# H3_MIDIController_Rev_3_MainBoard.net
KiCad netlist of a schematic drawn in EAGLE
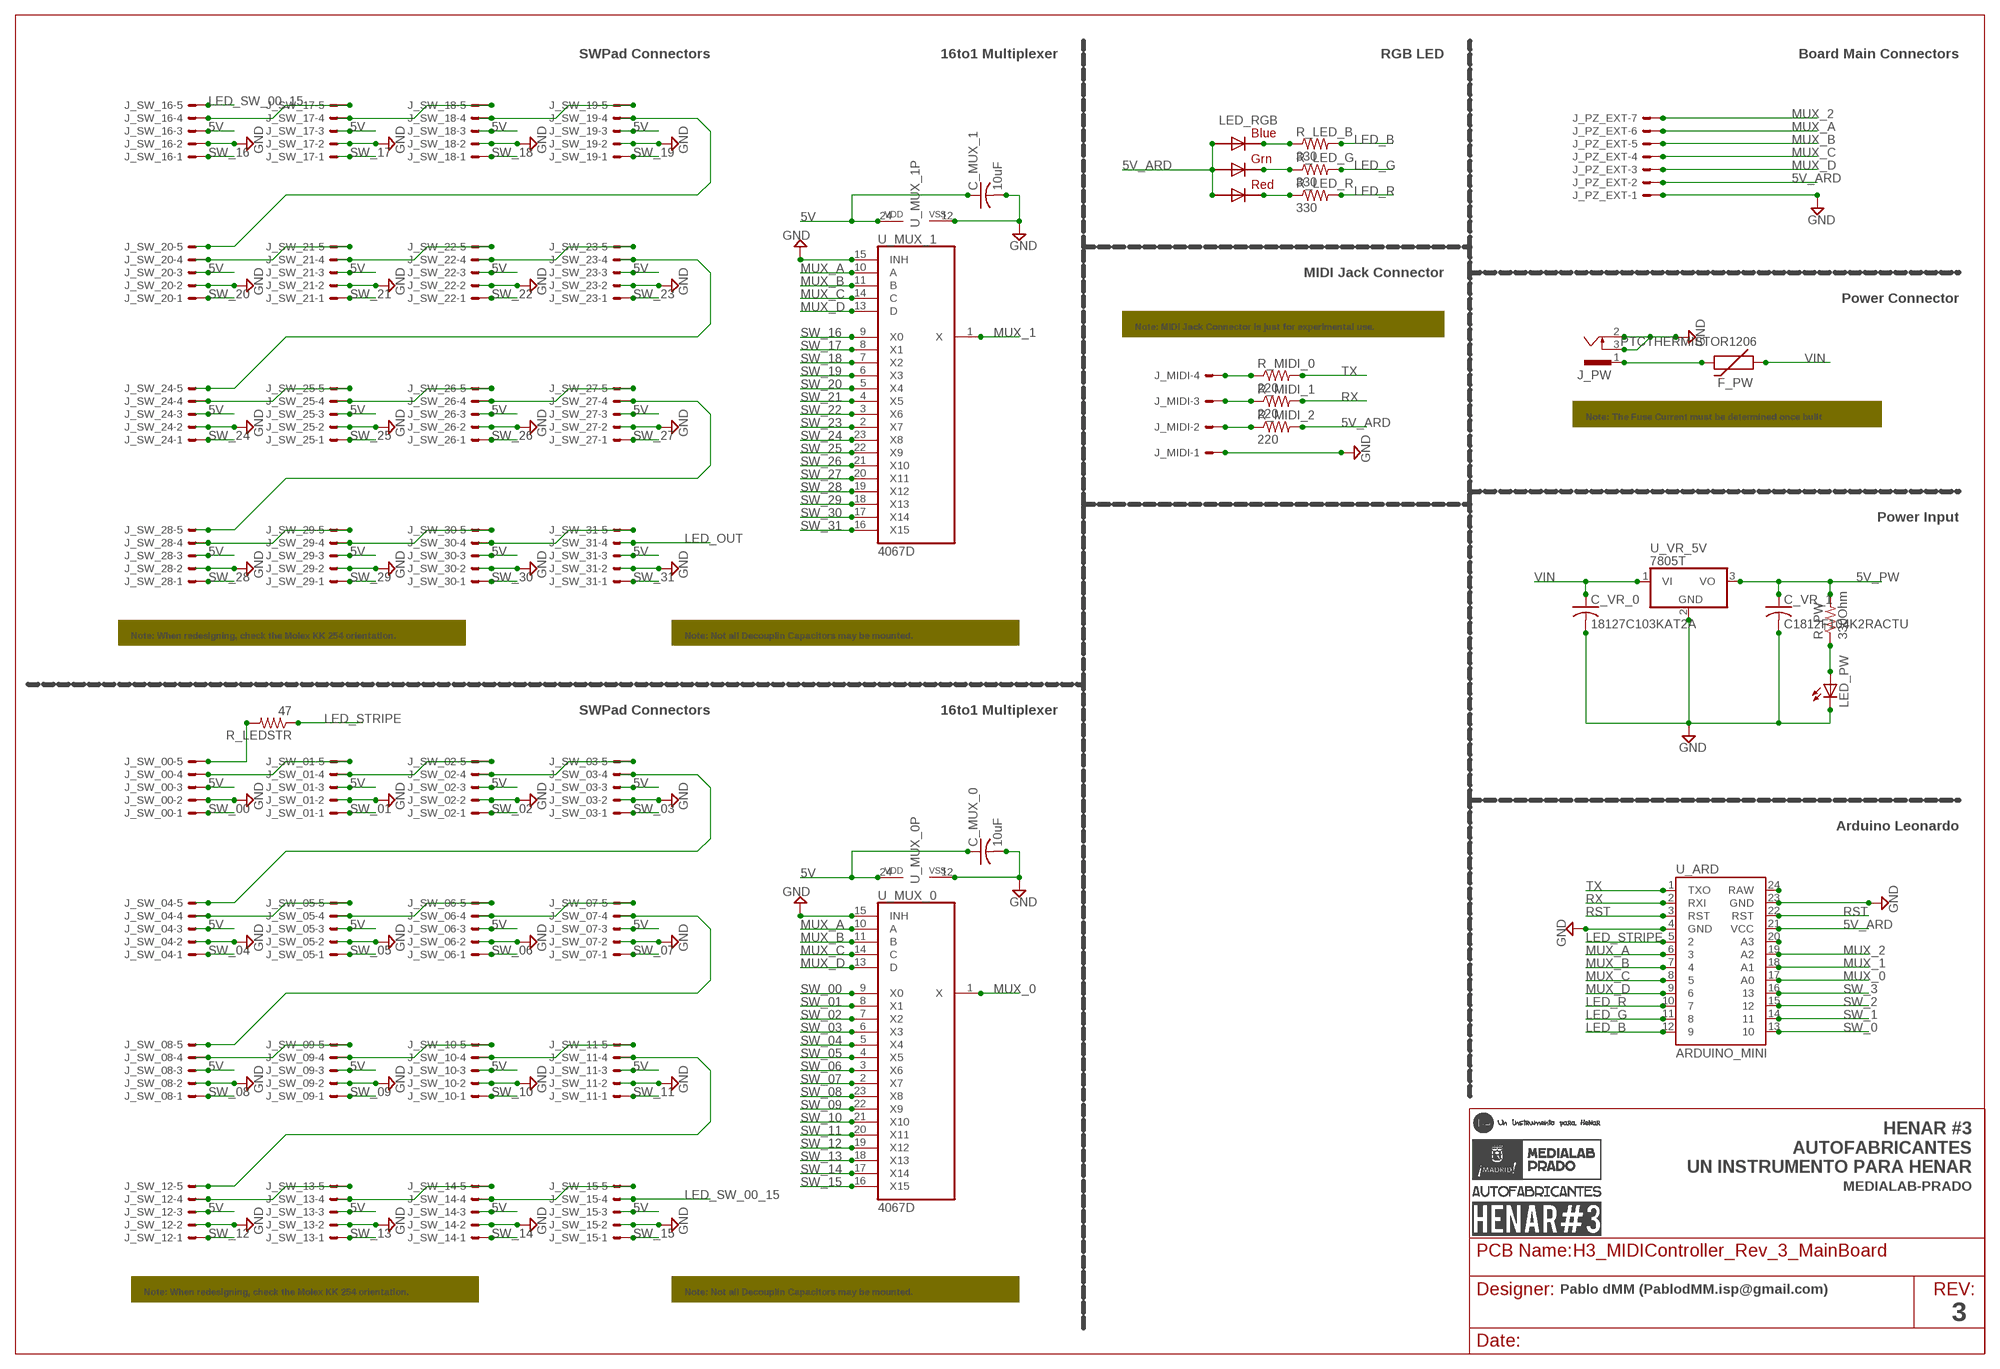
[diagram p0: schematic, sheet 1]

(export (version "E")
  (design (tool "Eeschema 10.0.6"))
  (components
    (comp (ref "C_MUX_0")
      (value "10uF")
      (footprint "eagle-import:C1206K")
      (libsource (lib "eagle-import") (part "C-USC1206K"))
    )
    (comp (ref "C_MUX_1")
      (value "10uF")
      (footprint "eagle-import:C1206K")
      (libsource (lib "eagle-import") (part "C-USC1206K"))
    )
    (comp (ref "C_VR_0")
      (value "18127C103KAT2A")
      (footprint "eagle-import:C1812K")
      (libsource (lib "eagle-import") (part "C-USC1812K"))
    )
    (comp (ref "C_VR_1")
      (value "C1812F104K2RACTU")
      (footprint "eagle-import:C1812K")
      (libsource (lib "eagle-import") (part "C-USC1812K"))
    )
    (comp (ref "F_PW")
      (value "PTCTHERMISTOR1206")
      (footprint "eagle-import:PTC-1206")
      (libsource (lib "eagle-import") (part "PTCTHERMISTOR1206"))
    )
    (comp (ref "J_MIDI")
      (value "22-05-7048-04")
      (footprint "eagle-import:7395-04")
      (libsource (lib "eagle-import") (part "22-?-0405-7048"))
    )
    (comp (ref "J_PW")
      (value "SCD-014A")
      (footprint "eagle-import:SCD-014-A")
      (libsource (lib "eagle-import") (part "SCD-014A"))
    )
    (comp (ref "J_PZ_EXT")
      (value "22-05-7078-07")
      (footprint "eagle-import:7395-07")
      (libsource (lib "eagle-import") (part "22-?-0705-7078"))
    )
    (comp (ref "J_SW_00")
      (value "22-05-7058-05")
      (footprint "eagle-import:7395-05")
      (libsource (lib "eagle-import") (part "22-?-0505-7058"))
    )
    (comp (ref "J_SW_01")
      (value "22-05-7058-05")
      (footprint "eagle-import:7395-05")
      (libsource (lib "eagle-import") (part "22-?-0505-7058"))
    )
    (comp (ref "J_SW_02")
      (value "22-05-7058-05")
      (footprint "eagle-import:7395-05")
      (libsource (lib "eagle-import") (part "22-?-0505-7058"))
    )
    (comp (ref "J_SW_03")
      (value "22-05-7058-05")
      (footprint "eagle-import:7395-05")
      (libsource (lib "eagle-import") (part "22-?-0505-7058"))
    )
    (comp (ref "J_SW_04")
      (value "22-05-7058-05")
      (footprint "eagle-import:7395-05")
      (libsource (lib "eagle-import") (part "22-?-0505-7058"))
    )
    (comp (ref "J_SW_05")
      (value "22-05-7058-05")
      (footprint "eagle-import:7395-05")
      (libsource (lib "eagle-import") (part "22-?-0505-7058"))
    )
    (comp (ref "J_SW_06")
      (value "22-05-7058-05")
      (footprint "eagle-import:7395-05")
      (libsource (lib "eagle-import") (part "22-?-0505-7058"))
    )
    (comp (ref "J_SW_07")
      (value "22-05-7058-05")
      (footprint "eagle-import:7395-05")
      (libsource (lib "eagle-import") (part "22-?-0505-7058"))
    )
    (comp (ref "J_SW_08")
      (value "22-05-7058-05")
      (footprint "eagle-import:7395-05")
      (libsource (lib "eagle-import") (part "22-?-0505-7058"))
    )
    (comp (ref "J_SW_09")
      (value "22-05-7058-05")
      (footprint "eagle-import:7395-05")
      (libsource (lib "eagle-import") (part "22-?-0505-7058"))
    )
    (comp (ref "J_SW_10")
      (value "22-05-7058-05")
      (footprint "eagle-import:7395-05")
      (libsource (lib "eagle-import") (part "22-?-0505-7058"))
    )
    (comp (ref "J_SW_11")
      (value "22-05-7058-05")
      (footprint "eagle-import:7395-05")
      (libsource (lib "eagle-import") (part "22-?-0505-7058"))
    )
    (comp (ref "J_SW_12")
      (value "22-05-7058-05")
      (footprint "eagle-import:7395-05")
      (libsource (lib "eagle-import") (part "22-?-0505-7058"))
    )
    (comp (ref "J_SW_13")
      (value "22-05-7058-05")
      (footprint "eagle-import:7395-05")
      (libsource (lib "eagle-import") (part "22-?-0505-7058"))
    )
    (comp (ref "J_SW_14")
      (value "22-05-7058-05")
      (footprint "eagle-import:7395-05")
      (libsource (lib "eagle-import") (part "22-?-0505-7058"))
    )
    (comp (ref "J_SW_15")
      (value "22-05-7058-05")
      (footprint "eagle-import:7395-05")
      (libsource (lib "eagle-import") (part "22-?-0505-7058"))
    )
    (comp (ref "J_SW_16")
      (value "22-05-7058-05")
      (footprint "eagle-import:7395-05")
      (libsource (lib "eagle-import") (part "22-?-0505-7058"))
    )
    (comp (ref "J_SW_17")
      (value "22-05-7058-05")
      (footprint "eagle-import:7395-05")
      (libsource (lib "eagle-import") (part "22-?-0505-7058"))
    )
    (comp (ref "J_SW_18")
      (value "22-05-7058-05")
      (footprint "eagle-import:7395-05")
      (libsource (lib "eagle-import") (part "22-?-0505-7058"))
    )
    (comp (ref "J_SW_19")
      (value "22-05-7058-05")
      (footprint "eagle-import:7395-05")
      (libsource (lib "eagle-import") (part "22-?-0505-7058"))
    )
    (comp (ref "J_SW_20")
      (value "22-05-7058-05")
      (footprint "eagle-import:7395-05")
      (libsource (lib "eagle-import") (part "22-?-0505-7058"))
    )
    (comp (ref "J_SW_21")
      (value "22-05-7058-05")
      (footprint "eagle-import:7395-05")
      (libsource (lib "eagle-import") (part "22-?-0505-7058"))
    )
    (comp (ref "J_SW_22")
      (value "22-05-7058-05")
      (footprint "eagle-import:7395-05")
      (libsource (lib "eagle-import") (part "22-?-0505-7058"))
    )
    (comp (ref "J_SW_23")
      (value "22-05-7058-05")
      (footprint "eagle-import:7395-05")
      (libsource (lib "eagle-import") (part "22-?-0505-7058"))
    )
    (comp (ref "J_SW_24")
      (value "22-05-7058-05")
      (footprint "eagle-import:7395-05")
      (libsource (lib "eagle-import") (part "22-?-0505-7058"))
    )
    (comp (ref "J_SW_25")
      (value "22-05-7058-05")
      (footprint "eagle-import:7395-05")
      (libsource (lib "eagle-import") (part "22-?-0505-7058"))
    )
    (comp (ref "J_SW_26")
      (value "22-05-7058-05")
      (footprint "eagle-import:7395-05")
      (libsource (lib "eagle-import") (part "22-?-0505-7058"))
    )
    (comp (ref "J_SW_27")
      (value "22-05-7058-05")
      (footprint "eagle-import:7395-05")
      (libsource (lib "eagle-import") (part "22-?-0505-7058"))
    )
    (comp (ref "J_SW_28")
      (value "22-05-7058-05")
      (footprint "eagle-import:7395-05")
      (libsource (lib "eagle-import") (part "22-?-0505-7058"))
    )
    (comp (ref "J_SW_29")
      (value "22-05-7058-05")
      (footprint "eagle-import:7395-05")
      (libsource (lib "eagle-import") (part "22-?-0505-7058"))
    )
    (comp (ref "J_SW_30")
      (value "22-05-7058-05")
      (footprint "eagle-import:7395-05")
      (libsource (lib "eagle-import") (part "22-?-0505-7058"))
    )
    (comp (ref "J_SW_31")
      (value "22-05-7058-05")
      (footprint "eagle-import:7395-05")
      (libsource (lib "eagle-import") (part "22-?-0505-7058"))
    )
    (comp (ref "LED_PW")
      (value "LEDSMT1206")
      (footprint "eagle-import:1206")
      (libsource (lib "eagle-import") (part "LEDSMT1206"))
    )
    (comp (ref "LED_RGB")
      (value "RGBLED5050")
      (footprint "eagle-import:RGBLED5050")
      (libsource (lib "eagle-import") (part "RGBLED5050"))
    )
    (comp (ref "R_LEDSTR")
      (value "47")
      (footprint "eagle-import:M1206")
      (libsource (lib "eagle-import") (part "R-US_M1206"))
    )
    (comp (ref "R_LED_B")
      (value "330")
      (footprint "eagle-import:M1206")
      (libsource (lib "eagle-import") (part "R-US_M1206"))
    )
    (comp (ref "R_LED_G")
      (value "330")
      (footprint "eagle-import:M1206")
      (libsource (lib "eagle-import") (part "R-US_M1206"))
    )
    (comp (ref "R_LED_R")
      (value "330")
      (footprint "eagle-import:M1206")
      (libsource (lib "eagle-import") (part "R-US_M1206"))
    )
    (comp (ref "R_MIDI_0")
      (value "220")
      (footprint "eagle-import:M1206")
      (libsource (lib "eagle-import") (part "R-US_M1206"))
    )
    (comp (ref "R_MIDI_1")
      (value "220")
      (footprint "eagle-import:M1206")
      (libsource (lib "eagle-import") (part "R-US_M1206"))
    )
    (comp (ref "R_MIDI_2")
      (value "220")
      (footprint "eagle-import:M1206")
      (libsource (lib "eagle-import") (part "R-US_M1206"))
    )
    (comp (ref "R_PW")
      (value "330Ohm")
      (footprint "eagle-import:M1206")
      (libsource (lib "eagle-import") (part "R-US_M1206"))
    )
    (comp (ref "U_ARD")
      (value "ARDUINO_MINI")
      (footprint "eagle-import:ARDUINO_MINI")
      (libsource (lib "eagle-import") (part "ARDUINO_MINI"))
    )
    (comp (ref "U_MUX_0")
      (value "4067D")
      (footprint "eagle-import:SO24W")
      (libsource (lib "eagle-import") (part "4067D"))
    )
    (comp (ref "U_MUX_1")
      (value "4067D")
      (footprint "eagle-import:SO24W")
      (libsource (lib "eagle-import") (part "4067D"))
    )
    (comp (ref "U_VR_5V")
      (value "7805T")
      (footprint "eagle-import:TO220H")
      (libsource (lib "eagle-import") (part "78T05"))
    )
  )
  (nets
    (net (code "1") (name "/5V") (class "Default")
      (node (ref "C_MUX_0") (pin "1") (pinfunction "1_1") (pintype "passive"))
      (node (ref "C_MUX_1") (pin "1") (pinfunction "1_1") (pintype "passive"))
      (node (ref "J_SW_00") (pin "3") (pinfunction "S_3") (pintype "passive"))
      (node (ref "J_SW_01") (pin "3") (pinfunction "S_3") (pintype "passive"))
      (node (ref "J_SW_02") (pin "3") (pinfunction "S_3") (pintype "passive"))
      (node (ref "J_SW_03") (pin "3") (pinfunction "S_3") (pintype "passive"))
      (node (ref "J_SW_04") (pin "3") (pinfunction "S_3") (pintype "passive"))
      (node (ref "J_SW_05") (pin "3") (pinfunction "S_3") (pintype "passive"))
      (node (ref "J_SW_06") (pin "3") (pinfunction "S_3") (pintype "passive"))
      (node (ref "J_SW_07") (pin "3") (pinfunction "S_3") (pintype "passive"))
      (node (ref "J_SW_08") (pin "3") (pinfunction "S_3") (pintype "passive"))
      (node (ref "J_SW_09") (pin "3") (pinfunction "S_3") (pintype "passive"))
      (node (ref "J_SW_10") (pin "3") (pinfunction "S_3") (pintype "passive"))
      (node (ref "J_SW_11") (pin "3") (pinfunction "S_3") (pintype "passive"))
      (node (ref "J_SW_12") (pin "3") (pinfunction "S_3") (pintype "passive"))
      (node (ref "J_SW_13") (pin "3") (pinfunction "S_3") (pintype "passive"))
      (node (ref "J_SW_14") (pin "3") (pinfunction "S_3") (pintype "passive"))
      (node (ref "J_SW_15") (pin "3") (pinfunction "S_3") (pintype "passive"))
      (node (ref "J_SW_16") (pin "3") (pinfunction "S_3") (pintype "passive"))
      (node (ref "J_SW_17") (pin "3") (pinfunction "S_3") (pintype "passive"))
      (node (ref "J_SW_18") (pin "3") (pinfunction "S_3") (pintype "passive"))
      (node (ref "J_SW_19") (pin "3") (pinfunction "S_3") (pintype "passive"))
      (node (ref "J_SW_20") (pin "3") (pinfunction "S_3") (pintype "passive"))
      (node (ref "J_SW_21") (pin "3") (pinfunction "S_3") (pintype "passive"))
      (node (ref "J_SW_22") (pin "3") (pinfunction "S_3") (pintype "passive"))
      (node (ref "J_SW_23") (pin "3") (pinfunction "S_3") (pintype "passive"))
      (node (ref "J_SW_24") (pin "3") (pinfunction "S_3") (pintype "passive"))
      (node (ref "J_SW_25") (pin "3") (pinfunction "S_3") (pintype "passive"))
      (node (ref "J_SW_26") (pin "3") (pinfunction "S_3") (pintype "passive"))
      (node (ref "J_SW_27") (pin "3") (pinfunction "S_3") (pintype "passive"))
      (node (ref "J_SW_28") (pin "3") (pinfunction "S_3") (pintype "passive"))
      (node (ref "J_SW_29") (pin "3") (pinfunction "S_3") (pintype "passive"))
      (node (ref "J_SW_30") (pin "3") (pinfunction "S_3") (pintype "passive"))
      (node (ref "J_SW_31") (pin "3") (pinfunction "S_3") (pintype "passive"))
      (node (ref "U_MUX_0") (pin "24") (pinfunction "VDD_24") (pintype "power_in"))
      (node (ref "U_MUX_1") (pin "24") (pinfunction "VDD_24") (pintype "power_in"))
    )
    (net (code "2") (name "/5V_ARD") (class "Default")
      (node (ref "J_PZ_EXT") (pin "2") (pinfunction "S_2") (pintype "passive"))
      (node (ref "LED_RGB") (pin "1") (pinfunction "GREEN_A_1") (pintype "bidirectional"))
      (node (ref "LED_RGB") (pin "2") (pinfunction "RED_A_2") (pintype "bidirectional"))
      (node (ref "LED_RGB") (pin "3") (pinfunction "BLUE_A_3") (pintype "bidirectional"))
      (node (ref "R_MIDI_2") (pin "2") (pinfunction "2_2") (pintype "passive"))
      (node (ref "U_ARD") (pin "21") (pinfunction "VCC_21") (pintype "bidirectional"))
    )
    (net (code "3") (name "/5V_PW") (class "Default")
      (node (ref "C_VR_1") (pin "1") (pinfunction "1_1") (pintype "passive"))
      (node (ref "R_PW") (pin "2") (pinfunction "2_2") (pintype "passive"))
      (node (ref "U_VR_5V") (pin "3") (pinfunction "VO_3") (pintype "passive"))
    )
    (net (code "4") (name "/LED_B") (class "Default")
      (node (ref "R_LED_B") (pin "2") (pinfunction "2_2") (pintype "passive"))
      (node (ref "U_ARD") (pin "12") (pinfunction "9_12") (pintype "bidirectional"))
    )
    (net (code "5") (name "/LED_G") (class "Default")
      (node (ref "R_LED_G") (pin "2") (pinfunction "2_2") (pintype "passive"))
      (node (ref "U_ARD") (pin "11") (pinfunction "8_11") (pintype "bidirectional"))
    )
    (net (code "6") (name "/LED_OUT") (class "Default")
      (node (ref "J_SW_31") (pin "4") (pinfunction "S_4") (pintype "passive"))
    )
    (net (code "7") (name "/LED_R") (class "Default")
      (node (ref "R_LED_R") (pin "2") (pinfunction "2_2") (pintype "passive"))
      (node (ref "U_ARD") (pin "10") (pinfunction "7_10") (pintype "bidirectional"))
    )
    (net (code "8") (name "/LED_STRIPE") (class "Default")
      (node (ref "R_LEDSTR") (pin "1") (pinfunction "1_1") (pintype "passive"))
      (node (ref "U_ARD") (pin "5") (pinfunction "2_5") (pintype "bidirectional"))
    )
    (net (code "9") (name "/LED_SW_00_15") (class "Default")
      (node (ref "J_SW_15") (pin "4") (pinfunction "S_4") (pintype "passive"))
      (node (ref "J_SW_16") (pin "5") (pinfunction "S_5") (pintype "passive"))
    )
    (net (code "10") (name "/MUX_0") (class "Default")
      (node (ref "U_ARD") (pin "17") (pinfunction "A0_17") (pintype "bidirectional"))
      (node (ref "U_MUX_0") (pin "1") (pinfunction "X_1") (pintype "output"))
    )
    (net (code "11") (name "/MUX_1") (class "Default")
      (node (ref "U_ARD") (pin "18") (pinfunction "A1_18") (pintype "bidirectional"))
      (node (ref "U_MUX_1") (pin "1") (pinfunction "X_1") (pintype "output"))
    )
    (net (code "12") (name "/MUX_2") (class "Default")
      (node (ref "J_PZ_EXT") (pin "7") (pinfunction "S_7") (pintype "passive"))
      (node (ref "U_ARD") (pin "19") (pinfunction "A2_19") (pintype "bidirectional"))
    )
    (net (code "13") (name "/MUX_A") (class "Default")
      (node (ref "J_PZ_EXT") (pin "6") (pinfunction "S_6") (pintype "passive"))
      (node (ref "U_ARD") (pin "6") (pinfunction "3_6") (pintype "bidirectional"))
      (node (ref "U_MUX_0") (pin "10") (pinfunction "A_10") (pintype "input"))
      (node (ref "U_MUX_1") (pin "10") (pinfunction "A_10") (pintype "input"))
    )
    (net (code "14") (name "/MUX_B") (class "Default")
      (node (ref "J_PZ_EXT") (pin "5") (pinfunction "S_5") (pintype "passive"))
      (node (ref "U_ARD") (pin "7") (pinfunction "4_7") (pintype "bidirectional"))
      (node (ref "U_MUX_0") (pin "11") (pinfunction "B_11") (pintype "input"))
      (node (ref "U_MUX_1") (pin "11") (pinfunction "B_11") (pintype "input"))
    )
    (net (code "15") (name "/MUX_C") (class "Default")
      (node (ref "J_PZ_EXT") (pin "4") (pinfunction "S_4") (pintype "passive"))
      (node (ref "U_ARD") (pin "8") (pinfunction "5_8") (pintype "bidirectional"))
      (node (ref "U_MUX_0") (pin "14") (pinfunction "C_14") (pintype "input"))
      (node (ref "U_MUX_1") (pin "14") (pinfunction "C_14") (pintype "input"))
    )
    (net (code "16") (name "/MUX_D") (class "Default")
      (node (ref "J_PZ_EXT") (pin "3") (pinfunction "S_3") (pintype "passive"))
      (node (ref "U_ARD") (pin "9") (pinfunction "6_9") (pintype "bidirectional"))
      (node (ref "U_MUX_0") (pin "13") (pinfunction "D_13") (pintype "input"))
      (node (ref "U_MUX_1") (pin "13") (pinfunction "D_13") (pintype "input"))
    )
    (net (code "17") (name "/RST") (class "Default")
      (node (ref "U_ARD") (pin "22") (pinfunction "RST_22") (pintype "bidirectional"))
      (node (ref "U_ARD") (pin "3") (pinfunction "RST_3") (pintype "bidirectional"))
    )
    (net (code "18") (name "/RX") (class "Default")
      (node (ref "R_MIDI_1") (pin "2") (pinfunction "2_2") (pintype "passive"))
      (node (ref "U_ARD") (pin "2") (pinfunction "RXI_2") (pintype "bidirectional"))
    )
    (net (code "19") (name "/SW_00") (class "Default")
      (node (ref "J_SW_00") (pin "1") (pinfunction "S_1") (pintype "passive"))
      (node (ref "U_MUX_0") (pin "9") (pinfunction "X0_9") (pintype "input"))
    )
    (net (code "20") (name "/SW_0") (class "Default")
      (node (ref "U_ARD") (pin "13") (pinfunction "10_13") (pintype "bidirectional"))
    )
    (net (code "21") (name "/SW_1") (class "Default")
      (node (ref "U_ARD") (pin "14") (pinfunction "11_14") (pintype "bidirectional"))
    )
    (net (code "22") (name "/SW_01") (class "Default")
      (node (ref "J_SW_01") (pin "1") (pinfunction "S_1") (pintype "passive"))
      (node (ref "U_MUX_0") (pin "8") (pinfunction "X1_8") (pintype "input"))
    )
    (net (code "23") (name "/SW_2") (class "Default")
      (node (ref "U_ARD") (pin "15") (pinfunction "12_15") (pintype "bidirectional"))
    )
    (net (code "24") (name "/SW_02") (class "Default")
      (node (ref "J_SW_02") (pin "1") (pinfunction "S_1") (pintype "passive"))
      (node (ref "U_MUX_0") (pin "7") (pinfunction "X2_7") (pintype "input"))
    )
    (net (code "25") (name "/SW_3") (class "Default")
      (node (ref "U_ARD") (pin "16") (pinfunction "13_16") (pintype "bidirectional"))
    )
    (net (code "26") (name "/SW_03") (class "Default")
      (node (ref "J_SW_03") (pin "1") (pinfunction "S_1") (pintype "passive"))
      (node (ref "U_MUX_0") (pin "6") (pinfunction "X3_6") (pintype "input"))
    )
    (net (code "27") (name "/SW_04") (class "Default")
      (node (ref "J_SW_04") (pin "1") (pinfunction "S_1") (pintype "passive"))
      (node (ref "U_MUX_0") (pin "5") (pinfunction "X4_5") (pintype "input"))
    )
    (net (code "28") (name "/SW_05") (class "Default")
      (node (ref "J_SW_05") (pin "1") (pinfunction "S_1") (pintype "passive"))
      (node (ref "U_MUX_0") (pin "4") (pinfunction "X5_4") (pintype "input"))
    )
    (net (code "29") (name "/SW_06") (class "Default")
      (node (ref "J_SW_06") (pin "1") (pinfunction "S_1") (pintype "passive"))
      (node (ref "U_MUX_0") (pin "3") (pinfunction "X6_3") (pintype "input"))
    )
    (net (code "30") (name "/SW_07") (class "Default")
      (node (ref "J_SW_07") (pin "1") (pinfunction "S_1") (pintype "passive"))
      (node (ref "U_MUX_0") (pin "2") (pinfunction "X7_2") (pintype "input"))
    )
    (net (code "31") (name "/SW_08") (class "Default")
      (node (ref "J_SW_08") (pin "1") (pinfunction "S_1") (pintype "passive"))
      (node (ref "U_MUX_0") (pin "23") (pinfunction "X8_23") (pintype "input"))
    )
    (net (code "32") (name "/SW_09") (class "Default")
      (node (ref "J_SW_09") (pin "1") (pinfunction "S_1") (pintype "passive"))
      (node (ref "U_MUX_0") (pin "22") (pinfunction "X9_22") (pintype "input"))
    )
    (net (code "33") (name "/SW_10") (class "Default")
      (node (ref "J_SW_10") (pin "1") (pinfunction "S_1") (pintype "passive"))
      (node (ref "U_MUX_0") (pin "21") (pinfunction "X10_21") (pintype "input"))
    )
    (net (code "34") (name "/SW_11") (class "Default")
      (node (ref "J_SW_11") (pin "1") (pinfunction "S_1") (pintype "passive"))
      (node (ref "U_MUX_0") (pin "20") (pinfunction "X11_20") (pintype "input"))
    )
    (net (code "35") (name "/SW_12") (class "Default")
      (node (ref "J_SW_12") (pin "1") (pinfunction "S_1") (pintype "passive"))
      (node (ref "U_MUX_0") (pin "19") (pinfunction "X12_19") (pintype "input"))
    )
    (net (code "36") (name "/SW_13") (class "Default")
      (node (ref "J_SW_13") (pin "1") (pinfunction "S_1") (pintype "passive"))
      (node (ref "U_MUX_0") (pin "18") (pinfunction "X13_18") (pintype "input"))
    )
    (net (code "37") (name "/SW_14") (class "Default")
      (node (ref "J_SW_14") (pin "1") (pinfunction "S_1") (pintype "passive"))
      (node (ref "U_MUX_0") (pin "17") (pinfunction "X14_17") (pintype "input"))
    )
    (net (code "38") (name "/SW_15") (class "Default")
      (node (ref "J_SW_15") (pin "1") (pinfunction "S_1") (pintype "passive"))
      (node (ref "U_MUX_0") (pin "16") (pinfunction "X15_16") (pintype "input"))
    )
    (net (code "39") (name "/SW_16") (class "Default")
      (node (ref "J_SW_16") (pin "1") (pinfunction "S_1") (pintype "passive"))
      (node (ref "U_MUX_1") (pin "9") (pinfunction "X0_9") (pintype "input"))
    )
    (net (code "40") (name "/SW_17") (class "Default")
      (node (ref "J_SW_17") (pin "1") (pinfunction "S_1") (pintype "passive"))
      (node (ref "U_MUX_1") (pin "8") (pinfunction "X1_8") (pintype "input"))
    )
    (net (code "41") (name "/SW_18") (class "Default")
      (node (ref "J_SW_18") (pin "1") (pinfunction "S_1") (pintype "passive"))
      (node (ref "U_MUX_1") (pin "7") (pinfunction "X2_7") (pintype "input"))
    )
    (net (code "42") (name "/SW_19") (class "Default")
      (node (ref "J_SW_19") (pin "1") (pinfunction "S_1") (pintype "passive"))
      (node (ref "U_MUX_1") (pin "6") (pinfunction "X3_6") (pintype "input"))
    )
    (net (code "43") (name "/SW_20") (class "Default")
      (node (ref "J_SW_20") (pin "1") (pinfunction "S_1") (pintype "passive"))
      (node (ref "U_MUX_1") (pin "5") (pinfunction "X4_5") (pintype "input"))
    )
    (net (code "44") (name "/SW_21") (class "Default")
      (node (ref "J_SW_21") (pin "1") (pinfunction "S_1") (pintype "passive"))
      (node (ref "U_MUX_1") (pin "4") (pinfunction "X5_4") (pintype "input"))
    )
    (net (code "45") (name "/SW_22") (class "Default")
      (node (ref "J_SW_22") (pin "1") (pinfunction "S_1") (pintype "passive"))
      (node (ref "U_MUX_1") (pin "3") (pinfunction "X6_3") (pintype "input"))
    )
    (net (code "46") (name "/SW_23") (class "Default")
      (node (ref "J_SW_23") (pin "1") (pinfunction "S_1") (pintype "passive"))
      (node (ref "U_MUX_1") (pin "2") (pinfunction "X7_2") (pintype "input"))
    )
    (net (code "47") (name "/SW_24") (class "Default")
      (node (ref "J_SW_24") (pin "1") (pinfunction "S_1") (pintype "passive"))
      (node (ref "U_MUX_1") (pin "23") (pinfunction "X8_23") (pintype "input"))
    )
    (net (code "48") (name "/SW_25") (class "Default")
      (node (ref "J_SW_25") (pin "1") (pinfunction "S_1") (pintype "passive"))
      (node (ref "U_MUX_1") (pin "22") (pinfunction "X9_22") (pintype "input"))
    )
    (net (code "49") (name "/SW_26") (class "Default")
      (node (ref "J_SW_26") (pin "1") (pinfunction "S_1") (pintype "passive"))
      (node (ref "U_MUX_1") (pin "21") (pinfunction "X10_21") (pintype "input"))
    )
    (net (code "50") (name "/SW_27") (class "Default")
      (node (ref "J_SW_27") (pin "1") (pinfunction "S_1") (pintype "passive"))
      (node (ref "U_MUX_1") (pin "20") (pinfunction "X11_20") (pintype "input"))
    )
    (net (code "51") (name "/SW_28") (class "Default")
      (node (ref "J_SW_28") (pin "1") (pinfunction "S_1") (pintype "passive"))
      (node (ref "U_MUX_1") (pin "19") (pinfunction "X12_19") (pintype "input"))
    )
    (net (code "52") (name "/SW_29") (class "Default")
      (node (ref "J_SW_29") (pin "1") (pinfunction "S_1") (pintype "passive"))
      (node (ref "U_MUX_1") (pin "18") (pinfunction "X13_18") (pintype "input"))
    )
    (net (code "53") (name "/SW_30") (class "Default")
      (node (ref "J_SW_30") (pin "1") (pinfunction "S_1") (pintype "passive"))
      (node (ref "U_MUX_1") (pin "17") (pinfunction "X14_17") (pintype "input"))
    )
    (net (code "54") (name "/SW_31") (class "Default")
      (node (ref "J_SW_31") (pin "1") (pinfunction "S_1") (pintype "passive"))
      (node (ref "U_MUX_1") (pin "16") (pinfunction "X15_16") (pintype "input"))
    )
    (net (code "55") (name "/TX") (class "Default")
      (node (ref "R_MIDI_0") (pin "2") (pinfunction "2_2") (pintype "passive"))
      (node (ref "U_ARD") (pin "1") (pinfunction "TXO_1") (pintype "bidirectional"))
    )
    (net (code "56") (name "/VIN") (class "Default")
      (node (ref "C_VR_0") (pin "1") (pinfunction "1_1") (pintype "passive"))
      (node (ref "F_PW") (pin "1") (pinfunction "1_1") (pintype "bidirectional"))
      (node (ref "U_VR_5V") (pin "1") (pinfunction "VI_1") (pintype "input"))
    )
    (net (code "57") (name "GND") (class "Default")
      (node (ref "C_MUX_0") (pin "2") (pinfunction "2_2") (pintype "passive"))
      (node (ref "C_MUX_1") (pin "2") (pinfunction "2_2") (pintype "passive"))
      (node (ref "C_VR_0") (pin "2") (pinfunction "2_2") (pintype "passive"))
      (node (ref "C_VR_1") (pin "2") (pinfunction "2_2") (pintype "passive"))
      (node (ref "J_MIDI") (pin "1") (pinfunction "S_1") (pintype "passive"))
      (node (ref "J_PW") (pin "2") (pinfunction "2_2") (pintype "passive"))
      (node (ref "J_PW") (pin "3") (pinfunction "3_3") (pintype "passive"))
      (node (ref "J_PZ_EXT") (pin "1") (pinfunction "S_1") (pintype "passive"))
      (node (ref "J_SW_00") (pin "2") (pinfunction "S_2") (pintype "passive"))
      (node (ref "J_SW_01") (pin "2") (pinfunction "S_2") (pintype "passive"))
      (node (ref "J_SW_02") (pin "2") (pinfunction "S_2") (pintype "passive"))
      (node (ref "J_SW_03") (pin "2") (pinfunction "S_2") (pintype "passive"))
      (node (ref "J_SW_04") (pin "2") (pinfunction "S_2") (pintype "passive"))
      (node (ref "J_SW_05") (pin "2") (pinfunction "S_2") (pintype "passive"))
      (node (ref "J_SW_06") (pin "2") (pinfunction "S_2") (pintype "passive"))
      (node (ref "J_SW_07") (pin "2") (pinfunction "S_2") (pintype "passive"))
      (node (ref "J_SW_08") (pin "2") (pinfunction "S_2") (pintype "passive"))
      (node (ref "J_SW_09") (pin "2") (pinfunction "S_2") (pintype "passive"))
      (node (ref "J_SW_10") (pin "2") (pinfunction "S_2") (pintype "passive"))
      (node (ref "J_SW_11") (pin "2") (pinfunction "S_2") (pintype "passive"))
      (node (ref "J_SW_12") (pin "2") (pinfunction "S_2") (pintype "passive"))
      (node (ref "J_SW_13") (pin "2") (pinfunction "S_2") (pintype "passive"))
      (node (ref "J_SW_14") (pin "2") (pinfunction "S_2") (pintype "passive"))
      (node (ref "J_SW_15") (pin "2") (pinfunction "S_2") (pintype "passive"))
      (node (ref "J_SW_16") (pin "2") (pinfunction "S_2") (pintype "passive"))
      (node (ref "J_SW_17") (pin "2") (pinfunction "S_2") (pintype "passive"))
      (node (ref "J_SW_18") (pin "2") (pinfunction "S_2") (pintype "passive"))
      (node (ref "J_SW_19") (pin "2") (pinfunction "S_2") (pintype "passive"))
      (node (ref "J_SW_20") (pin "2") (pinfunction "S_2") (pintype "passive"))
      (node (ref "J_SW_21") (pin "2") (pinfunction "S_2") (pintype "passive"))
      (node (ref "J_SW_22") (pin "2") (pinfunction "S_2") (pintype "passive"))
      (node (ref "J_SW_23") (pin "2") (pinfunction "S_2") (pintype "passive"))
      (node (ref "J_SW_24") (pin "2") (pinfunction "S_2") (pintype "passive"))
      (node (ref "J_SW_25") (pin "2") (pinfunction "S_2") (pintype "passive"))
      (node (ref "J_SW_26") (pin "2") (pinfunction "S_2") (pintype "passive"))
      (node (ref "J_SW_27") (pin "2") (pinfunction "S_2") (pintype "passive"))
      (node (ref "J_SW_28") (pin "2") (pinfunction "S_2") (pintype "passive"))
      (node (ref "J_SW_29") (pin "2") (pinfunction "S_2") (pintype "passive"))
      (node (ref "J_SW_30") (pin "2") (pinfunction "S_2") (pintype "passive"))
      (node (ref "J_SW_31") (pin "2") (pinfunction "S_2") (pintype "passive"))
      (node (ref "LED_PW") (pin "C") (pinfunction "C_C") (pintype "passive"))
      (node (ref "U_ARD") (pin "23") (pinfunction "GND_23") (pintype "bidirectional"))
      (node (ref "U_ARD") (pin "4") (pinfunction "GND_4") (pintype "bidirectional"))
      (node (ref "U_MUX_0") (pin "12") (pinfunction "VSS_12") (pintype "power_in"))
      (node (ref "U_MUX_0") (pin "15") (pinfunction "INH_15") (pintype "input"))
      (node (ref "U_MUX_1") (pin "12") (pinfunction "VSS_12") (pintype "power_in"))
      (node (ref "U_MUX_1") (pin "15") (pinfunction "INH_15") (pintype "input"))
      (node (ref "U_VR_5V") (pin "2") (pinfunction "GND_2") (pintype "passive"))
    )
    (net (code "58") (name "Net-(F_PW-Pad2)") (class "Default")
      (node (ref "F_PW") (pin "2") (pinfunction "2_2") (pintype "bidirectional"))
      (node (ref "J_PW") (pin "1") (pinfunction "1_1") (pintype "passive"))
    )
    (net (code "59") (name "Net-(J_MIDIB-S)") (class "Default")
      (node (ref "J_MIDI") (pin "2") (pinfunction "S_2") (pintype "passive"))
      (node (ref "R_MIDI_2") (pin "1") (pinfunction "1_1") (pintype "passive"))
    )
    (net (code "60") (name "Net-(J_MIDIC-S)") (class "Default")
      (node (ref "J_MIDI") (pin "3") (pinfunction "S_3") (pintype "passive"))
      (node (ref "R_MIDI_1") (pin "1") (pinfunction "1_1") (pintype "passive"))
    )
    (net (code "61") (name "Net-(J_MIDID-S)") (class "Default")
      (node (ref "J_MIDI") (pin "4") (pinfunction "S_4") (pintype "passive"))
      (node (ref "R_MIDI_0") (pin "1") (pinfunction "1_1") (pintype "passive"))
    )
    (net (code "62") (name "Net-(J_SW_00D-S)") (class "Default")
      (node (ref "J_SW_00") (pin "4") (pinfunction "S_4") (pintype "passive"))
      (node (ref "J_SW_01") (pin "5") (pinfunction "S_5") (pintype "passive"))
    )
    (net (code "63") (name "Net-(J_SW_00E-S)") (class "Default")
      (node (ref "J_SW_00") (pin "5") (pinfunction "S_5") (pintype "passive"))
      (node (ref "R_LEDSTR") (pin "2") (pinfunction "2_2") (pintype "passive"))
    )
    (net (code "64") (name "Net-(J_SW_01D-S)") (class "Default")
      (node (ref "J_SW_01") (pin "4") (pinfunction "S_4") (pintype "passive"))
      (node (ref "J_SW_02") (pin "5") (pinfunction "S_5") (pintype "passive"))
    )
    (net (code "65") (name "Net-(J_SW_02D-S)") (class "Default")
      (node (ref "J_SW_02") (pin "4") (pinfunction "S_4") (pintype "passive"))
      (node (ref "J_SW_03") (pin "5") (pinfunction "S_5") (pintype "passive"))
    )
    (net (code "66") (name "Net-(J_SW_03D-S)") (class "Default")
      (node (ref "J_SW_03") (pin "4") (pinfunction "S_4") (pintype "passive"))
      (node (ref "J_SW_04") (pin "5") (pinfunction "S_5") (pintype "passive"))
    )
    (net (code "67") (name "Net-(J_SW_04D-S)") (class "Default")
      (node (ref "J_SW_04") (pin "4") (pinfunction "S_4") (pintype "passive"))
      (node (ref "J_SW_05") (pin "5") (pinfunction "S_5") (pintype "passive"))
    )
    (net (code "68") (name "Net-(J_SW_05D-S)") (class "Default")
      (node (ref "J_SW_05") (pin "4") (pinfunction "S_4") (pintype "passive"))
      (node (ref "J_SW_06") (pin "5") (pinfunction "S_5") (pintype "passive"))
    )
    (net (code "69") (name "Net-(J_SW_06D-S)") (class "Default")
      (node (ref "J_SW_06") (pin "4") (pinfunction "S_4") (pintype "passive"))
      (node (ref "J_SW_07") (pin "5") (pinfunction "S_5") (pintype "passive"))
    )
    (net (code "70") (name "Net-(J_SW_07D-S)") (class "Default")
      (node (ref "J_SW_07") (pin "4") (pinfunction "S_4") (pintype "passive"))
      (node (ref "J_SW_08") (pin "5") (pinfunction "S_5") (pintype "passive"))
    )
    (net (code "71") (name "Net-(J_SW_08D-S)") (class "Default")
      (node (ref "J_SW_08") (pin "4") (pinfunction "S_4") (pintype "passive"))
      (node (ref "J_SW_09") (pin "5") (pinfunction "S_5") (pintype "passive"))
    )
    (net (code "72") (name "Net-(J_SW_09D-S)") (class "Default")
      (node (ref "J_SW_09") (pin "4") (pinfunction "S_4") (pintype "passive"))
      (node (ref "J_SW_10") (pin "5") (pinfunction "S_5") (pintype "passive"))
    )
    (net (code "73") (name "Net-(J_SW_10D-S)") (class "Default")
      (node (ref "J_SW_10") (pin "4") (pinfunction "S_4") (pintype "passive"))
      (node (ref "J_SW_11") (pin "5") (pinfunction "S_5") (pintype "passive"))
    )
    (net (code "74") (name "Net-(J_SW_11D-S)") (class "Default")
      (node (ref "J_SW_11") (pin "4") (pinfunction "S_4") (pintype "passive"))
      (node (ref "J_SW_12") (pin "5") (pinfunction "S_5") (pintype "passive"))
    )
    (net (code "75") (name "Net-(J_SW_12D-S)") (class "Default")
      (node (ref "J_SW_12") (pin "4") (pinfunction "S_4") (pintype "passive"))
      (node (ref "J_SW_13") (pin "5") (pinfunction "S_5") (pintype "passive"))
    )
    (net (code "76") (name "Net-(J_SW_13D-S)") (class "Default")
      (node (ref "J_SW_13") (pin "4") (pinfunction "S_4") (pintype "passive"))
      (node (ref "J_SW_14") (pin "5") (pinfunction "S_5") (pintype "passive"))
    )
    (net (code "77") (name "Net-(J_SW_14D-S)") (class "Default")
      (node (ref "J_SW_14") (pin "4") (pinfunction "S_4") (pintype "passive"))
      (node (ref "J_SW_15") (pin "5") (pinfunction "S_5") (pintype "passive"))
    )
    (net (code "78") (name "Net-(J_SW_16D-S)") (class "Default")
      (node (ref "J_SW_16") (pin "4") (pinfunction "S_4") (pintype "passive"))
      (node (ref "J_SW_17") (pin "5") (pinfunction "S_5") (pintype "passive"))
    )
    (net (code "79") (name "Net-(J_SW_17D-S)") (class "Default")
      (node (ref "J_SW_17") (pin "4") (pinfunction "S_4") (pintype "passive"))
      (node (ref "J_SW_18") (pin "5") (pinfunction "S_5") (pintype "passive"))
    )
    (net (code "80") (name "Net-(J_SW_18D-S)") (class "Default")
      (node (ref "J_SW_18") (pin "4") (pinfunction "S_4") (pintype "passive"))
      (node (ref "J_SW_19") (pin "5") (pinfunction "S_5") (pintype "passive"))
    )
    (net (code "81") (name "Net-(J_SW_19D-S)") (class "Default")
      (node (ref "J_SW_19") (pin "4") (pinfunction "S_4") (pintype "passive"))
      (node (ref "J_SW_20") (pin "5") (pinfunction "S_5") (pintype "passive"))
    )
    (net (code "82") (name "Net-(J_SW_20D-S)") (class "Default")
      (node (ref "J_SW_20") (pin "4") (pinfunction "S_4") (pintype "passive"))
      (node (ref "J_SW_21") (pin "5") (pinfunction "S_5") (pintype "passive"))
    )
    (net (code "83") (name "Net-(J_SW_21D-S)") (class "Default")
      (node (ref "J_SW_21") (pin "4") (pinfunction "S_4") (pintype "passive"))
      (node (ref "J_SW_22") (pin "5") (pinfunction "S_5") (pintype "passive"))
    )
    (net (code "84") (name "Net-(J_SW_22D-S)") (class "Default")
      (node (ref "J_SW_22") (pin "4") (pinfunction "S_4") (pintype "passive"))
      (node (ref "J_SW_23") (pin "5") (pinfunction "S_5") (pintype "passive"))
    )
    (net (code "85") (name "Net-(J_SW_23D-S)") (class "Default")
      (node (ref "J_SW_23") (pin "4") (pinfunction "S_4") (pintype "passive"))
      (node (ref "J_SW_24") (pin "5") (pinfunction "S_5") (pintype "passive"))
    )
    (net (code "86") (name "Net-(J_SW_24D-S)") (class "Default")
      (node (ref "J_SW_24") (pin "4") (pinfunction "S_4") (pintype "passive"))
      (node (ref "J_SW_25") (pin "5") (pinfunction "S_5") (pintype "passive"))
    )
    (net (code "87") (name "Net-(J_SW_25D-S)") (class "Default")
      (node (ref "J_SW_25") (pin "4") (pinfunction "S_4") (pintype "passive"))
      (node (ref "J_SW_26") (pin "5") (pinfunction "S_5") (pintype "passive"))
    )
    (net (code "88") (name "Net-(J_SW_26D-S)") (class "Default")
      (node (ref "J_SW_26") (pin "4") (pinfunction "S_4") (pintype "passive"))
      (node (ref "J_SW_27") (pin "5") (pinfunction "S_5") (pintype "passive"))
    )
    (net (code "89") (name "Net-(J_SW_27D-S)") (class "Default")
      (node (ref "J_SW_27") (pin "4") (pinfunction "S_4") (pintype "passive"))
      (node (ref "J_SW_28") (pin "5") (pinfunction "S_5") (pintype "passive"))
    )
    (net (code "90") (name "Net-(J_SW_28D-S)") (class "Default")
      (node (ref "J_SW_28") (pin "4") (pinfunction "S_4") (pintype "passive"))
      (node (ref "J_SW_29") (pin "5") (pinfunction "S_5") (pintype "passive"))
    )
    (net (code "91") (name "Net-(J_SW_29D-S)") (class "Default")
      (node (ref "J_SW_29") (pin "4") (pinfunction "S_4") (pintype "passive"))
      (node (ref "J_SW_30") (pin "5") (pinfunction "S_5") (pintype "passive"))
    )
    (net (code "92") (name "Net-(J_SW_30D-S)") (class "Default")
      (node (ref "J_SW_30") (pin "4") (pinfunction "S_4") (pintype "passive"))
      (node (ref "J_SW_31") (pin "5") (pinfunction "S_5") (pintype "passive"))
    )
    (net (code "93") (name "Net-(LED_PW-PadA)") (class "Default")
      (node (ref "LED_PW") (pin "A") (pinfunction "A_A") (pintype "passive"))
      (node (ref "R_PW") (pin "1") (pinfunction "1_1") (pintype "passive"))
    )
    (net (code "94") (name "Net-(LED_RGB-BLUE_C)") (class "Default")
      (node (ref "LED_RGB") (pin "4") (pinfunction "BLUE_C_4") (pintype "bidirectional"))
      (node (ref "R_LED_B") (pin "1") (pinfunction "1_1") (pintype "passive"))
    )
    (net (code "95") (name "Net-(LED_RGB-GREEN_C)") (class "Default")
      (node (ref "LED_RGB") (pin "6") (pinfunction "GREEN_C_6") (pintype "bidirectional"))
      (node (ref "R_LED_G") (pin "1") (pinfunction "1_1") (pintype "passive"))
    )
    (net (code "96") (name "Net-(LED_RGB-RED_C)") (class "Default")
      (node (ref "LED_RGB") (pin "5") (pinfunction "RED_C_5") (pintype "bidirectional"))
      (node (ref "R_LED_R") (pin "1") (pinfunction "1_1") (pintype "passive"))
    )
    (net (code "97") (name "unconnected-(U_ARD-A3-Pad20)") (class "Default")
      (node (ref "U_ARD") (pin "20") (pinfunction "A3_20") (pintype "bidirectional"))
    )
    (net (code "98") (name "unconnected-(U_ARD-RAW-Pad24)") (class "Default")
      (node (ref "U_ARD") (pin "24") (pinfunction "RAW_24") (pintype "bidirectional"))
    )
  )
)
